# IO.net
KiCad netlist of a schematic drawn in Altium Designer
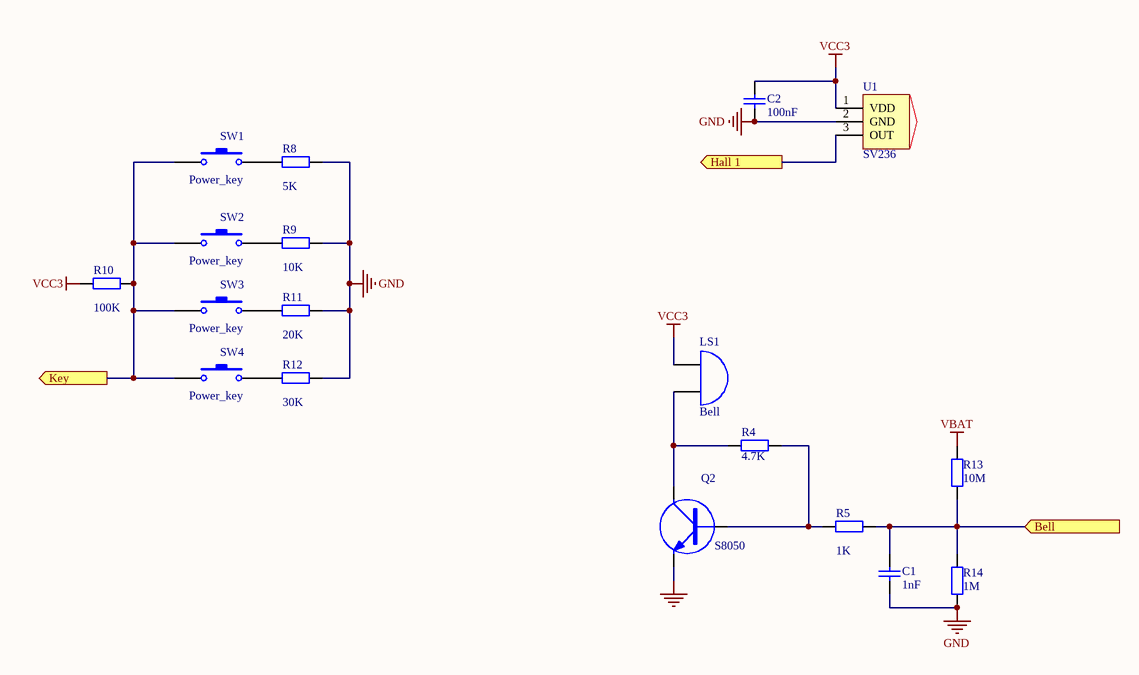
[diagram p0: IO.SchDoc]

(export (version "E")
  (design (tool "Eeschema 10.0.6"))
  (components
    (comp (ref "C1")
      (value "1nF")
      (footprint "RAD-0.3")
      (description "Capacitor")
      (fields (field (name "Comment") "Cap") (field (name "PUBLISHER") "Altium Limited"))
      (libsource (lib "Miscellaneous Devices") (part "Cap"))
    )
    (comp (ref "C2")
      (value "100nF")
      (footprint "RAD-0.3")
      (description "Capacitor")
      (fields (field (name "Comment") "Cap") (field (name "PUBLISHER") "Altium Limited"))
      (libsource (lib "Miscellaneous Devices") (part "Cap"))
    )
    (comp (ref "LS1")
      (value "Bell")
      (description "Electrical Bell")
      (fields (field (name "PUBLISHER") "Altium Limited"))
      (libsource (lib "Miscellaneous Devices") (part "Bell"))
    )
    (comp (ref "Q2")
      (value "S8050")
      (footprint "SOT-23")
      (description "NPN Transistor")
      (libsource (lib "*") (part "NPN"))
    )
    (comp (ref "R4")
      (value "4.7K")
      (description "Resistor")
      (fields (field (name "Comment") "100K") (field (name "PUBLISHER") "Altium Limited"))
      (libsource (lib "") (part "Res2_2"))
    )
    (comp (ref "R5")
      (value "1K")
      (description "Resistor")
      (fields (field (name "Comment") "Res2") (field (name "PUBLISHER") "Altium Limited"))
      (libsource (lib "") (part "Res2_1"))
    )
    (comp (ref "R8")
      (value "5K")
      (description "Resistor")
      (fields (field (name "Comment") "Res2") (field (name "PUBLISHER") "Altium Limited"))
      (libsource (lib "") (part "Res2_1"))
    )
    (comp (ref "R9")
      (value "10K")
      (description "Resistor")
      (fields (field (name "Comment") "Res2") (field (name "PUBLISHER") "Altium Limited"))
      (libsource (lib "") (part "Res2_1"))
    )
    (comp (ref "R10")
      (value "100K")
      (description "Resistor")
      (fields (field (name "Comment") "Res2") (field (name "PUBLISHER") "Altium Limited"))
      (libsource (lib "") (part "Res2_1"))
    )
    (comp (ref "R11")
      (value "20K")
      (description "Resistor")
      (fields (field (name "Comment") "Res2") (field (name "PUBLISHER") "Altium Limited"))
      (libsource (lib "") (part "Res2_1"))
    )
    (comp (ref "R12")
      (value "30K")
      (description "Resistor")
      (fields (field (name "Comment") "Res2") (field (name "PUBLISHER") "Altium Limited"))
      (libsource (lib "") (part "Res2_1"))
    )
    (comp (ref "R13")
      (value "10M")
      (description "Resistor")
      (fields (field (name "Comment") "Res2") (field (name "PUBLISHER") "Altium Limited"))
      (libsource (lib "Miscellaneous Devices") (part "Res2"))
    )
    (comp (ref "R14")
      (value "1M")
      (description "Resistor")
      (fields (field (name "Comment") "Res2") (field (name "PUBLISHER") "Altium Limited"))
      (libsource (lib "Miscellaneous Devices") (part "Res2"))
    )
    (comp (ref "SW1")
      (value "Power_key")
      (description "Switch")
      (fields (field (name "PUBLISHER") "Altium Limited"))
      (libsource (lib "Miscellaneous Devices") (part "SW-PB"))
    )
    (comp (ref "SW2")
      (value "Power_key")
      (description "Switch")
      (fields (field (name "PUBLISHER") "Altium Limited"))
      (libsource (lib "Miscellaneous Devices") (part "SW-PB"))
    )
    (comp (ref "SW3")
      (value "Power_key")
      (description "Switch")
      (fields (field (name "PUBLISHER") "Altium Limited"))
      (libsource (lib "Miscellaneous Devices") (part "SW-PB"))
    )
    (comp (ref "SW4")
      (value "Power_key")
      (description "Switch")
      (fields (field (name "PUBLISHER") "Altium Limited"))
      (libsource (lib "Miscellaneous Devices") (part "SW-PB"))
    )
    (comp (ref "U1") (value "SV236") (footprint "sot-23-3") (libsource (lib "*") (part "霍尔44E 938")))
  )
  (nets
    (net (code "1") (name "/Bell") (class "Default")
      (node (ref "C1") (pin "1") (pinfunction "1_1") (pintype "passive"))
      (node (ref "R13") (pin "1") (pinfunction "1_1") (pintype "passive"))
      (node (ref "R14") (pin "2") (pinfunction "2_2") (pintype "passive"))
      (node (ref "R5") (pin "2") (pinfunction "2_2") (pintype "passive"))
    )
    (net (code "2") (name "/Hall 1") (class "Default")
      (node (ref "U1") (pin "3") (pinfunction "OUT_3") (pintype "passive"))
    )
    (net (code "3") (name "/Key") (class "Default")
      (node (ref "R10") (pin "2") (pinfunction "2_2") (pintype "passive"))
      (node (ref "SW1") (pin "1") (pinfunction "1_1") (pintype "passive"))
      (node (ref "SW2") (pin "1") (pinfunction "1_1") (pintype "passive"))
      (node (ref "SW3") (pin "1") (pinfunction "1_1") (pintype "passive"))
      (node (ref "SW4") (pin "1") (pinfunction "1_1") (pintype "passive"))
    )
    (net (code "4") (name "GND") (class "Default")
      (node (ref "C1") (pin "2") (pinfunction "2_2") (pintype "passive"))
      (node (ref "C2") (pin "2") (pinfunction "2_2") (pintype "passive"))
      (node (ref "Q2") (pin "2") (pinfunction "E_2") (pintype "passive"))
      (node (ref "R11") (pin "2") (pinfunction "2_2") (pintype "passive"))
      (node (ref "R12") (pin "2") (pinfunction "2_2") (pintype "passive"))
      (node (ref "R14") (pin "1") (pinfunction "1_1") (pintype "passive"))
      (node (ref "R8") (pin "2") (pinfunction "2_2") (pintype "passive"))
      (node (ref "R9") (pin "2") (pinfunction "2_2") (pintype "passive"))
      (node (ref "U1") (pin "2") (pinfunction "GND_2") (pintype "passive"))
    )
    (net (code "5") (name "Net-(LS1-B)") (class "Default")
      (node (ref "LS1") (pin "2") (pinfunction "B_2") (pintype "passive"))
      (node (ref "Q2") (pin "3") (pinfunction "C_3") (pintype "passive"))
      (node (ref "R4") (pin "2") (pinfunction "2_2") (pintype "passive"))
    )
    (net (code "6") (name "Net-(Q2-B)") (class "Default")
      (node (ref "Q2") (pin "1") (pinfunction "B_1") (pintype "passive"))
      (node (ref "R4") (pin "1") (pinfunction "1_1") (pintype "passive"))
      (node (ref "R5") (pin "1") (pinfunction "1_1") (pintype "passive"))
    )
    (net (code "7") (name "Net-(R8-Pad1)") (class "Default")
      (node (ref "R8") (pin "1") (pinfunction "1_1") (pintype "passive"))
      (node (ref "SW1") (pin "2") (pinfunction "2_2") (pintype "passive"))
    )
    (net (code "8") (name "Net-(R9-Pad1)") (class "Default")
      (node (ref "R9") (pin "1") (pinfunction "1_1") (pintype "passive"))
      (node (ref "SW2") (pin "2") (pinfunction "2_2") (pintype "passive"))
    )
    (net (code "9") (name "Net-(R11-Pad1)") (class "Default")
      (node (ref "R11") (pin "1") (pinfunction "1_1") (pintype "passive"))
      (node (ref "SW3") (pin "2") (pinfunction "2_2") (pintype "passive"))
    )
    (net (code "10") (name "Net-(R12-Pad1)") (class "Default")
      (node (ref "R12") (pin "1") (pinfunction "1_1") (pintype "passive"))
      (node (ref "SW4") (pin "2") (pinfunction "2_2") (pintype "passive"))
    )
    (net (code "11") (name "VBAT") (class "Default")
      (node (ref "R13") (pin "2") (pinfunction "2_2") (pintype "passive"))
    )
    (net (code "12") (name "VCC3") (class "Default")
      (node (ref "C2") (pin "1") (pinfunction "1_1") (pintype "passive"))
      (node (ref "LS1") (pin "1") (pinfunction "A_1") (pintype "passive"))
      (node (ref "R10") (pin "1") (pinfunction "1_1") (pintype "passive"))
      (node (ref "U1") (pin "1") (pinfunction "VDD_1") (pintype "passive"))
    )
  )
)
